# Base_Schematic.net
KiCad netlist of a schematic drawn in Altium Designer
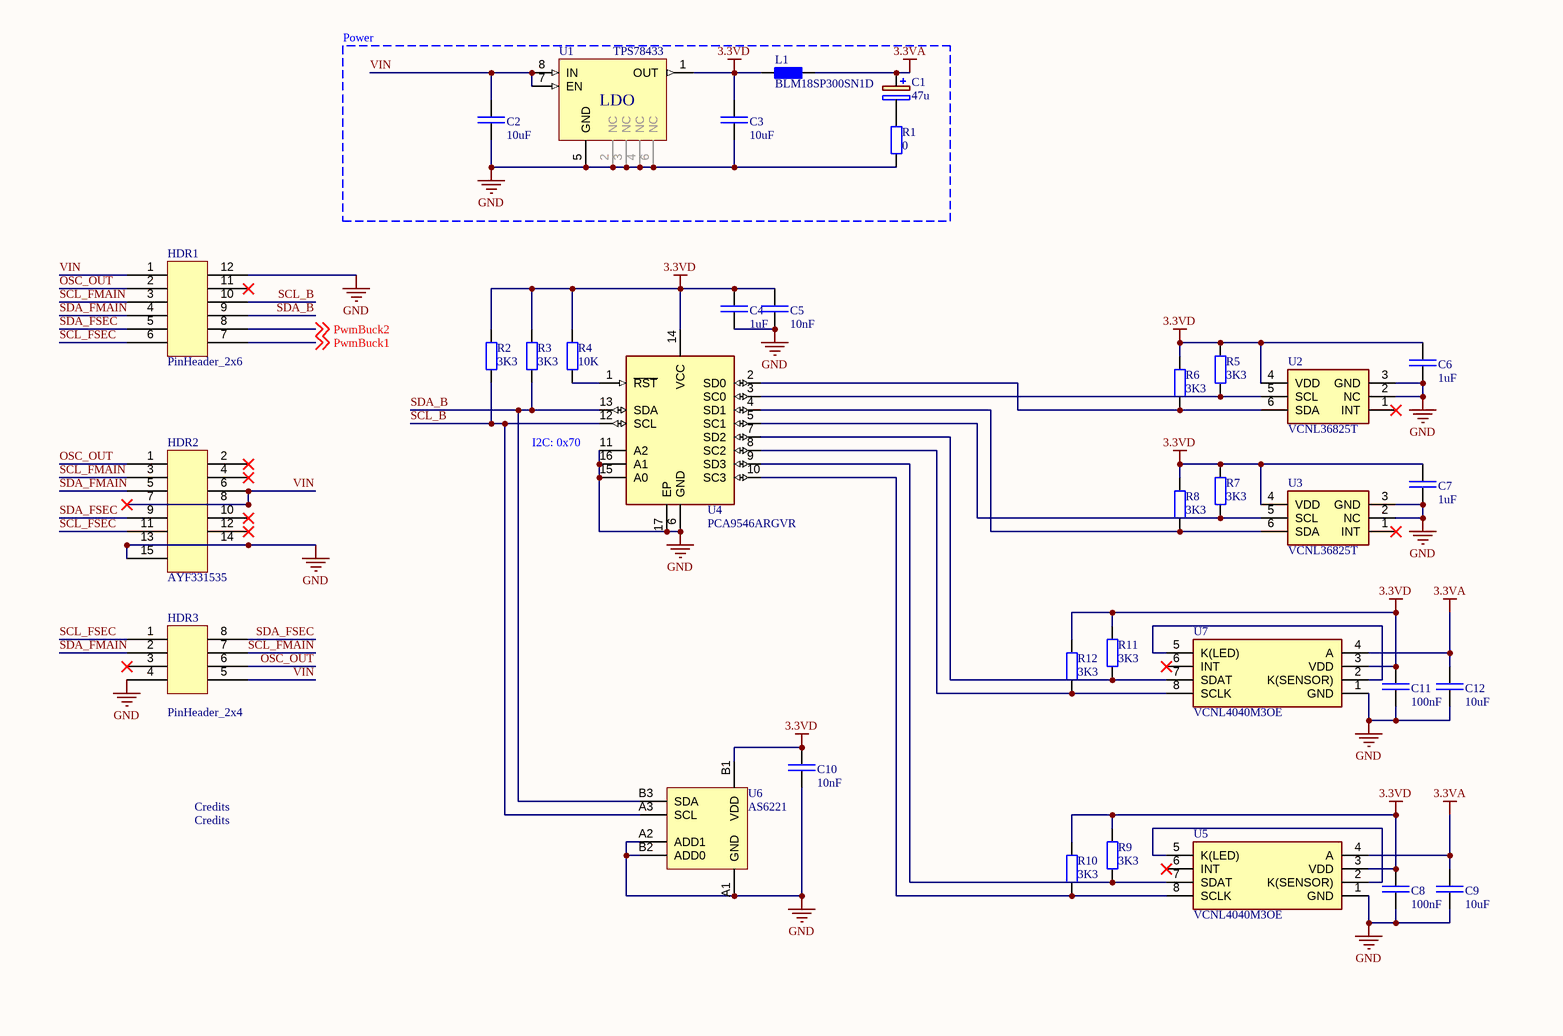
[diagram p0: Base_Schematic.SchDoc]

(export (version "E")
  (design (tool "Eeschema 10.0.6"))
  (components
    (comp (ref "C1")
      (value "47u")
      (footprint "CAPAE7366X61N")
      (description "Aluminium Electrolytic Capacitors - SMD 47uF 25V")
      (libsource (lib "Base_Symbols") (part "EEE-FK1E470P"))
    )
    (comp (ref "C2")
      (value "10uF")
      (footprint "CAP_SM0805_YAGEOCC2_N")
      (description "CAP 10uF SM0805 X5R 16V YAGEO CC2")
      (fields
        (field (name "MANUFACTURER") "Yageo")
        (field (name "MANUFACTURER PART NUMBER") "CC0805KKX7R8BB225")
      )
      (libsource (lib "Base_Symbols") (part "CC0805KKX5R8BB106"))
    )
    (comp (ref "C3")
      (value "10uF")
      (footprint "CAP_SM0805_YAGEOCC2_N")
      (description "CAP 10uF SM0805 X5R 16V YAGEO CC2")
      (fields
        (field (name "MANUFACTURER") "Yageo")
        (field (name "MANUFACTURER PART NUMBER") "CC0805KKX7R8BB225")
      )
      (libsource (lib "Base_Symbols") (part "CC0805KKX5R8BB106"))
    )
    (comp (ref "C4")
      (value "1uF")
      (footprint "CAP_SM0805_YAGEOCC2_N")
      (description "CAP 1uF SM0805 X7R 25V YAGEO CC2")
      (fields
        (field (name "MANUFACTURER") "Yageo")
        (field (name "MANUFACTURER PART NUMBER") "CC0805KKX7R8BB105")
      )
      (libsource (lib "Base_Symbols") (part "CC0805KKX7R8BB105"))
    )
    (comp (ref "C5")
      (value "10nF")
      (footprint "CAP_SM0402_YAGEOCC2_N")
      (description "CAP 10nF SM0402 X7R 50V YAGEO CC2")
      (fields
        (field (name "MANUFACTURER") "Yageo")
        (field (name "MANUFACTURER PART NUMBER") "CC0603KRX7R9BB103")
      )
      (libsource (lib "Base_Symbols") (part "CC0402KRX7R9BB103"))
    )
    (comp (ref "C6")
      (value "1uF")
      (footprint "CAP_SM0805_YAGEOCC2_N")
      (description "CAP 1uF SM0805 X7R 25V YAGEO CC2")
      (fields
        (field (name "MANUFACTURER") "Yageo")
        (field (name "MANUFACTURER PART NUMBER") "CC0805KKX7R8BB105")
      )
      (libsource (lib "Base_Symbols") (part "CC0805KKX7R8BB105"))
    )
    (comp (ref "C7")
      (value "1uF")
      (footprint "CAP_SM0805_YAGEOCC2_N")
      (description "CAP 1uF SM0805 X7R 25V YAGEO CC2")
      (fields
        (field (name "MANUFACTURER") "Yageo")
        (field (name "MANUFACTURER PART NUMBER") "CC0805KKX7R8BB105")
      )
      (libsource (lib "Base_Symbols") (part "CC0805KKX7R8BB105"))
    )
    (comp (ref "C8")
      (value "100nF")
      (footprint "CAP_SM0603_YAGEOCC2_N")
      (description "CAP 100nF SM0603 X7R 50V YAGEO CC2")
      (fields
        (field (name "MANUFACTURER") "Yageo")
        (field (name "MANUFACTURER PART NUMBER") "CC0603KRX7R9BB104")
      )
      (libsource (lib "Base_Symbols") (part "CC0603KRX7R9BB104"))
    )
    (comp (ref "C9")
      (value "10uF")
      (footprint "CAP_SM0805_YAGEOCC2_N")
      (description "CAP 10uF SM0805 X5R 16V YAGEO CC2")
      (fields
        (field (name "MANUFACTURER") "Yageo")
        (field (name "MANUFACTURER PART NUMBER") "CC0805KKX7R8BB225")
      )
      (libsource (lib "Base_Symbols") (part "CC0805KKX5R8BB106"))
    )
    (comp (ref "C10")
      (value "10nF")
      (footprint "CAP_SM0402_YAGEOCC2_N")
      (description "CAP 10nF SM0402 X7R 50V YAGEO CC2")
      (fields
        (field (name "MANUFACTURER") "Yageo")
        (field (name "MANUFACTURER PART NUMBER") "CC0603KRX7R9BB103")
      )
      (libsource (lib "Base_Symbols") (part "CC0402KRX7R9BB103"))
    )
    (comp (ref "C11")
      (value "100nF")
      (footprint "CAP_SM0603_YAGEOCC2_N")
      (description "CAP 100nF SM0603 X7R 50V YAGEO CC2")
      (fields
        (field (name "MANUFACTURER") "Yageo")
        (field (name "MANUFACTURER PART NUMBER") "CC0603KRX7R9BB104")
      )
      (libsource (lib "Base_Symbols") (part "CC0603KRX7R9BB104"))
    )
    (comp (ref "C12")
      (value "10uF")
      (footprint "CAP_SM0805_YAGEOCC2_N")
      (description "CAP 10uF SM0805 X5R 16V YAGEO CC2")
      (fields
        (field (name "MANUFACTURER") "Yageo")
        (field (name "MANUFACTURER PART NUMBER") "CC0805KKX7R8BB225")
      )
      (libsource (lib "Base_Symbols") (part "CC0805KKX5R8BB106"))
    )
    (comp (ref "Credit")
      (value "Credits")
      (footprint "CREDITS_CU+TS_SIGNED")
      (libsource (lib "Base_Symbols") (part "Credits"))
    )
    (comp (ref "HDR1")
      (value "PinHeader_2x6")
      (footprint "PinHeader_2x6_2.54mm")
      (description "PinHeader_2x6 2.54mm Pitch")
      (libsource (lib "Base_Symbols") (part "PinHeader_2x6_2.54mm"))
    )
    (comp (ref "HDR2")
      (value "AYF331535")
      (footprint "AYF331535 _Reverse")
      (description "AYF331535 FFC & FPC-Steckverbinder CONNECTOR SURFACE MOUNT")
      (libsource (lib "Base_Symbols") (part "AYF331535"))
    )
    (comp (ref "HDR3")
      (value "PinHeader_2x4")
      (footprint "PinHeader_2x4_2.54mm")
      (description "PinHeader_2x4 2.54mm Pitch")
      (libsource (lib "Base_Symbols") (part "PinHeader_2x4_2.54mm"))
    )
    (comp (ref "L1")
      (value "BLM18SP300SN1D")
      (footprint "Chip2PinSM127P600-8N")
      (description "Ferrite Beads 0603 30ohm 10% 6A")
      (fields (field (name "MOUSER PART NUMBER") "81-BLM18SP300SN1D"))
      (libsource (lib "Base_Symbols") (part "BLM18SP300SN1D"))
    )
    (comp (ref "R1")
      (value "0")
      (footprint "RES_SM0603_YAGEORC_N")
      (description "RES 0R SM0603 YAGEO RC_L")
      (fields
        (field (name "MANUFACTURER") "Yageo")
        (field (name "MANUFACTURER PART NUMBER") "RC0603FR-0710KL")
      )
      (libsource (lib "Base_Symbols") (part "RC0603FR-070RL"))
    )
    (comp (ref "R2")
      (value "3K3")
      (footprint "RES_SM0603_YAGEORC_N")
      (description "RES 3K3 SM0603 YAGEO RC_L")
      (fields
        (field (name "MANUFACTURER") "Yageo")
        (field (name "MANUFACTURER PART NUMBER") "RC0603FR-0710KL")
      )
      (libsource (lib "") (part "RC0603FR-073K3L_1"))
    )
    (comp (ref "R3")
      (value "3K3")
      (footprint "RES_SM0603_YAGEORC_N")
      (description "RES 3K3 SM0603 YAGEO RC_L")
      (fields
        (field (name "MANUFACTURER") "Yageo")
        (field (name "MANUFACTURER PART NUMBER") "RC0603FR-0710KL")
      )
      (libsource (lib "") (part "RC0603FR-073K3L_1"))
    )
    (comp (ref "R4")
      (value "10K")
      (footprint "RES_SM0603_YAGEORC_N")
      (description "RES 10K SM0603 YAGEO RC_L")
      (fields
        (field (name "MANUFACTURER") "Yageo")
        (field (name "MANUFACTURER PART NUMBER") "RC0603FR-0710KL")
      )
      (libsource (lib "Base_Symbols") (part "RC0603FR-0710KL"))
    )
    (comp (ref "R5")
      (value "3K3")
      (footprint "RES_SM0603_YAGEORC_N")
      (description "RES 3K3 SM0603 YAGEO RC_L")
      (fields
        (field (name "MANUFACTURER") "Yageo")
        (field (name "MANUFACTURER PART NUMBER") "RC0603FR-0710KL")
      )
      (libsource (lib "Base_Symbols") (part "RC0603FR-073K3L"))
    )
    (comp (ref "R6")
      (value "3K3")
      (footprint "RES_SM0603_YAGEORC_N")
      (description "RES 3K3 SM0603 YAGEO RC_L")
      (fields
        (field (name "MANUFACTURER") "Yageo")
        (field (name "MANUFACTURER PART NUMBER") "RC0603FR-0710KL")
      )
      (libsource (lib "Base_Symbols") (part "RC0603FR-073K3L"))
    )
    (comp (ref "R7")
      (value "3K3")
      (footprint "RES_SM0603_YAGEORC_N")
      (description "RES 3K3 SM0603 YAGEO RC_L")
      (fields
        (field (name "MANUFACTURER") "Yageo")
        (field (name "MANUFACTURER PART NUMBER") "RC0603FR-0710KL")
      )
      (libsource (lib "Base_Symbols") (part "RC0603FR-073K3L"))
    )
    (comp (ref "R8")
      (value "3K3")
      (footprint "RES_SM0603_YAGEORC_N")
      (description "RES 3K3 SM0603 YAGEO RC_L")
      (fields
        (field (name "MANUFACTURER") "Yageo")
        (field (name "MANUFACTURER PART NUMBER") "RC0603FR-0710KL")
      )
      (libsource (lib "Base_Symbols") (part "RC0603FR-073K3L"))
    )
    (comp (ref "R9")
      (value "3K3")
      (footprint "RES_SM0603_YAGEORC_N")
      (description "RES 3K3 SM0603 YAGEO RC_L")
      (fields
        (field (name "MANUFACTURER") "Yageo")
        (field (name "MANUFACTURER PART NUMBER") "RC0603FR-0710KL")
      )
      (libsource (lib "Base_Symbols") (part "RC0603FR-073K3L"))
    )
    (comp (ref "R10")
      (value "3K3")
      (footprint "RES_SM0603_YAGEORC_N")
      (description "RES 3K3 SM0603 YAGEO RC_L")
      (fields
        (field (name "MANUFACTURER") "Yageo")
        (field (name "MANUFACTURER PART NUMBER") "RC0603FR-0710KL")
      )
      (libsource (lib "Base_Symbols") (part "RC0603FR-073K3L"))
    )
    (comp (ref "R11")
      (value "3K3")
      (footprint "RES_SM0603_YAGEORC_N")
      (description "RES 3K3 SM0603 YAGEO RC_L")
      (fields
        (field (name "MANUFACTURER") "Yageo")
        (field (name "MANUFACTURER PART NUMBER") "RC0603FR-0710KL")
      )
      (libsource (lib "Base_Symbols") (part "RC0603FR-073K3L"))
    )
    (comp (ref "R12")
      (value "3K3")
      (footprint "RES_SM0603_YAGEORC_N")
      (description "RES 3K3 SM0603 YAGEO RC_L")
      (fields
        (field (name "MANUFACTURER") "Yageo")
        (field (name "MANUFACTURER PART NUMBER") "RC0603FR-0710KL")
      )
      (libsource (lib "Base_Symbols") (part "RC0603FR-073K3L"))
    )
    (comp (ref "U1")
      (value "TPS78433")
      (footprint "TPS784xxxQDRBRQ1_SON")
      (libsource (lib "Base_Symbols") (part "TPS78433QWDRBRQ1"))
    )
    (comp (ref "U2")
      (value "VCNL36825T")
      (footprint "VCNL36825T")
      (description "Proximity Sensors PROX SENS INTER VCSEL I2C-E4, IC SENSORS")
      (fields (field (name "MOUSER PART NUMBER") "78-VCNL36825T"))
      (libsource (lib "Base_Symbols") (part "VCNL36825T"))
    )
    (comp (ref "U3")
      (value "VCNL36825T")
      (footprint "VCNL36825T")
      (description "Proximity Sensors PROX SENS INTER VCSEL I2C-E4, IC SENSORS")
      (fields (field (name "MOUSER PART NUMBER") "78-VCNL36825T"))
      (libsource (lib "Base_Symbols") (part "VCNL36825T"))
    )
    (comp (ref "U4")
      (value "PCA9546ARGVR")
      (footprint "QFN65P400X400X100-17N-D")
      (description "4-Channel I2C And SMBus Switch With Reset Functions")
      (fields (field (name "MOUSER PART NUMBER") "595-PCA9546ARGVR"))
      (libsource (lib "Base_Symbols") (part "PCA9546ARGVR"))
    )
    (comp (ref "U5")
      (value "VCNL4040M3OE")
      (footprint "VCNL4040M3OE")
      (fields (field (name "MOUSER PART NUMBER") "78-VCNL4040M3OE"))
      (libsource (lib "Base_Symbols") (part "VCNL4040M3OE"))
    )
    (comp (ref "U6")
      (value "AS6221")
      (footprint "AS6221_BGA_LargePads")
      (description "AS6221 Temperature Sensor Digital -40°C ~ 125°C 16b 6-WLCSP (1.5x1.03)")
      (libsource (lib "Base_Symbols") (part "AS6221-AWLT-S"))
    )
    (comp (ref "U7")
      (value "VCNL4040M3OE")
      (footprint "VCNL4040M3OE")
      (fields (field (name "MOUSER PART NUMBER") "78-VCNL4040M3OE"))
      (libsource (lib "Base_Symbols") (part "VCNL4040M3OE"))
    )
  )
  (nets
    (net (code "1") (name "/OSC_OUT") (class "Default")
      (node (ref "HDR1") (pin "2") (pintype "passive"))
      (node (ref "HDR2") (pin "1") (pintype "passive"))
      (node (ref "HDR3") (pin "6") (pintype "passive"))
    )
    (net (code "2") (name "/SCL_B") (class "Default")
      (node (ref "HDR1") (pin "10") (pintype "passive"))
      (node (ref "R2") (pin "2") (pintype "passive"))
      (node (ref "U4") (pin "12") (pinfunction "SCL_12") (pintype "bidirectional"))
      (node (ref "U6") (pin "A3") (pinfunction "SCL_A3") (pintype "passive"))
    )
    (net (code "3") (name "/SCL_FMAIN") (class "Default")
      (node (ref "HDR1") (pin "3") (pintype "passive"))
      (node (ref "HDR2") (pin "3") (pintype "passive"))
      (node (ref "HDR3") (pin "7") (pintype "passive"))
    )
    (net (code "4") (name "/SCL_FSEC") (class "Default")
      (node (ref "HDR1") (pin "6") (pintype "passive"))
      (node (ref "HDR2") (pin "11") (pintype "passive"))
      (node (ref "HDR3") (pin "1") (pintype "passive"))
    )
    (net (code "5") (name "/SDA_B") (class "Default")
      (node (ref "HDR1") (pin "9") (pintype "passive"))
      (node (ref "R3") (pin "2") (pintype "passive"))
      (node (ref "U4") (pin "13") (pinfunction "SDA_13") (pintype "bidirectional"))
      (node (ref "U6") (pin "B3") (pinfunction "SDA_B3") (pintype "passive"))
    )
    (net (code "6") (name "/SDA_FMAIN") (class "Default")
      (node (ref "HDR1") (pin "4") (pintype "passive"))
      (node (ref "HDR2") (pin "5") (pintype "passive"))
      (node (ref "HDR3") (pin "2") (pintype "passive"))
    )
    (net (code "7") (name "/SDA_FSEC") (class "Default")
      (node (ref "HDR1") (pin "5") (pintype "passive"))
      (node (ref "HDR2") (pin "9") (pintype "passive"))
      (node (ref "HDR3") (pin "8") (pintype "passive"))
    )
    (net (code "8") (name "/VIN") (class "Default")
      (node (ref "C2") (pin "1") (pintype "passive"))
      (node (ref "HDR1") (pin "1") (pintype "passive"))
      (node (ref "HDR2") (pin "6") (pintype "passive"))
      (node (ref "HDR2") (pin "7") (pintype "passive"))
      (node (ref "HDR2") (pin "8") (pintype "passive"))
      (node (ref "HDR3") (pin "5") (pintype "passive"))
      (node (ref "U1") (pin "7") (pinfunction "EN_7") (pintype "input"))
      (node (ref "U1") (pin "8") (pinfunction "IN_8") (pintype "input"))
    )
    (net (code "9") (name "3.3VA") (class "Default")
      (node (ref "C1") (pin "1") (pinfunction "+_1") (pintype "passive"))
      (node (ref "C12") (pin "1") (pintype "passive"))
      (node (ref "C9") (pin "1") (pintype "passive"))
      (node (ref "L1") (pin "2") (pintype "passive"))
      (node (ref "U5") (pin "4") (pinfunction "A_4") (pintype "passive"))
      (node (ref "U7") (pin "4") (pinfunction "A_4") (pintype "passive"))
    )
    (net (code "10") (name "3.3VD") (class "Default")
      (node (ref "C10") (pin "1") (pintype "passive"))
      (node (ref "C11") (pin "1") (pintype "passive"))
      (node (ref "C3") (pin "1") (pintype "passive"))
      (node (ref "C4") (pin "1") (pintype "passive"))
      (node (ref "C5") (pin "1") (pintype "passive"))
      (node (ref "C6") (pin "1") (pintype "passive"))
      (node (ref "C7") (pin "1") (pintype "passive"))
      (node (ref "C8") (pin "1") (pintype "passive"))
      (node (ref "L1") (pin "1") (pintype "passive"))
      (node (ref "R10") (pin "2") (pintype "passive"))
      (node (ref "R11") (pin "2") (pintype "passive"))
      (node (ref "R12") (pin "2") (pintype "passive"))
      (node (ref "R2") (pin "1") (pintype "passive"))
      (node (ref "R3") (pin "1") (pintype "passive"))
      (node (ref "R4") (pin "1") (pintype "passive"))
      (node (ref "R5") (pin "2") (pintype "passive"))
      (node (ref "R6") (pin "2") (pintype "passive"))
      (node (ref "R7") (pin "2") (pintype "passive"))
      (node (ref "R8") (pin "2") (pintype "passive"))
      (node (ref "R9") (pin "2") (pintype "passive"))
      (node (ref "U1") (pin "1") (pinfunction "OUT_1") (pintype "output"))
      (node (ref "U2") (pin "4") (pinfunction "VDD_4") (pintype "passive"))
      (node (ref "U3") (pin "4") (pinfunction "VDD_4") (pintype "passive"))
      (node (ref "U4") (pin "14") (pinfunction "VCC_14") (pintype "passive"))
      (node (ref "U5") (pin "3") (pinfunction "VDD_3") (pintype "passive"))
      (node (ref "U6") (pin "B1") (pinfunction "VDD_B1") (pintype "passive"))
      (node (ref "U7") (pin "3") (pinfunction "VDD_3") (pintype "passive"))
    )
    (net (code "11") (name "GND") (class "Default")
      (node (ref "C10") (pin "2") (pintype "passive"))
      (node (ref "C11") (pin "2") (pintype "passive"))
      (node (ref "C12") (pin "2") (pintype "passive"))
      (node (ref "C2") (pin "2") (pintype "passive"))
      (node (ref "C3") (pin "2") (pintype "passive"))
      (node (ref "C4") (pin "2") (pintype "passive"))
      (node (ref "C5") (pin "2") (pintype "passive"))
      (node (ref "C6") (pin "2") (pintype "passive"))
      (node (ref "C7") (pin "2") (pintype "passive"))
      (node (ref "C8") (pin "2") (pintype "passive"))
      (node (ref "C9") (pin "2") (pintype "passive"))
      (node (ref "HDR1") (pin "12") (pintype "passive"))
      (node (ref "HDR2") (pin "13") (pintype "passive"))
      (node (ref "HDR2") (pin "14") (pintype "passive"))
      (node (ref "HDR2") (pin "15") (pintype "passive"))
      (node (ref "HDR3") (pin "4") (pintype "passive"))
      (node (ref "R1") (pin "1") (pintype "passive"))
      (node (ref "U1") (pin "2") (pinfunction "NC_2") (pintype "passive"))
      (node (ref "U1") (pin "3") (pinfunction "NC_3") (pintype "passive"))
      (node (ref "U1") (pin "4") (pinfunction "NC_4") (pintype "passive"))
      (node (ref "U1") (pin "5") (pinfunction "GND_5") (pintype "passive"))
      (node (ref "U1") (pin "6") (pinfunction "NC_6") (pintype "passive"))
      (node (ref "U2") (pin "2") (pinfunction "NC_2") (pintype "passive"))
      (node (ref "U2") (pin "3") (pinfunction "GND_3") (pintype "passive"))
      (node (ref "U3") (pin "2") (pinfunction "NC_2") (pintype "passive"))
      (node (ref "U3") (pin "3") (pinfunction "GND_3") (pintype "passive"))
      (node (ref "U4") (pin "11") (pinfunction "A2_11") (pintype "passive"))
      (node (ref "U4") (pin "15") (pinfunction "A0_15") (pintype "passive"))
      (node (ref "U4") (pin "16") (pinfunction "A1_16") (pintype "passive"))
      (node (ref "U4") (pin "17") (pinfunction "EP_17") (pintype "passive"))
      (node (ref "U4") (pin "6") (pinfunction "GND_6") (pintype "passive"))
      (node (ref "U5") (pin "1") (pinfunction "GND_1") (pintype "passive"))
      (node (ref "U6") (pin "A1") (pinfunction "GND_A1") (pintype "passive"))
      (node (ref "U6") (pin "A2") (pinfunction "ADD1_A2") (pintype "passive"))
      (node (ref "U6") (pin "B2") (pinfunction "ADD0_B2") (pintype "passive"))
      (node (ref "U7") (pin "1") (pinfunction "GND_1") (pintype "passive"))
    )
    (net (code "12") (name "Net-(C1--)") (class "Default")
      (node (ref "C1") (pin "2") (pinfunction "-_2") (pintype "passive"))
      (node (ref "R1") (pin "2") (pintype "passive"))
    )
    (net (code "13") (name "Net-(U2-SCL)") (class "Default")
      (node (ref "R5") (pin "1") (pintype "passive"))
      (node (ref "U2") (pin "5") (pinfunction "SCL_5") (pintype "passive"))
      (node (ref "U4") (pin "3") (pinfunction "SC0_3") (pintype "bidirectional"))
    )
    (net (code "14") (name "Net-(U2-SDA)") (class "Default")
      (node (ref "R6") (pin "1") (pintype "passive"))
      (node (ref "U2") (pin "6") (pinfunction "SDA_6") (pintype "passive"))
      (node (ref "U4") (pin "2") (pinfunction "SD0_2") (pintype "bidirectional"))
    )
    (net (code "15") (name "Net-(U3-SCL)") (class "Default")
      (node (ref "R7") (pin "1") (pintype "passive"))
      (node (ref "U3") (pin "5") (pinfunction "SCL_5") (pintype "passive"))
      (node (ref "U4") (pin "5") (pinfunction "SC1_5") (pintype "bidirectional"))
    )
    (net (code "16") (name "Net-(U3-SDA)") (class "Default")
      (node (ref "R8") (pin "1") (pintype "passive"))
      (node (ref "U3") (pin "6") (pinfunction "SDA_6") (pintype "passive"))
      (node (ref "U4") (pin "4") (pinfunction "SD1_4") (pintype "bidirectional"))
    )
    (net (code "17") (name "Net-(U4-SC2)") (class "Default")
      (node (ref "R12") (pin "1") (pintype "passive"))
      (node (ref "U4") (pin "8") (pinfunction "SC2_8") (pintype "bidirectional"))
      (node (ref "U7") (pin "8") (pinfunction "SCLK_8") (pintype "passive"))
    )
    (net (code "18") (name "Net-(U4-SC3)") (class "Default")
      (node (ref "R10") (pin "1") (pintype "passive"))
      (node (ref "U4") (pin "10") (pinfunction "SC3_10") (pintype "bidirectional"))
      (node (ref "U5") (pin "8") (pinfunction "SCLK_8") (pintype "passive"))
    )
    (net (code "19") (name "Net-(U4-SD2)") (class "Default")
      (node (ref "R11") (pin "1") (pintype "passive"))
      (node (ref "U4") (pin "7") (pinfunction "SD2_7") (pintype "bidirectional"))
      (node (ref "U7") (pin "7") (pinfunction "SDAT_7") (pintype "passive"))
    )
    (net (code "20") (name "Net-(U4-SD3)") (class "Default")
      (node (ref "R9") (pin "1") (pintype "passive"))
      (node (ref "U4") (pin "9") (pinfunction "SD3_9") (pintype "bidirectional"))
      (node (ref "U5") (pin "7") (pinfunction "SDAT_7") (pintype "passive"))
    )
    (net (code "21") (name "Net-(U4-~{RST})") (class "Default")
      (node (ref "R4") (pin "2") (pintype "passive"))
      (node (ref "U4") (pin "1") (pinfunction "~{RST}_1") (pintype "input"))
    )
    (net (code "22") (name "Net-(U5-K(LED))") (class "Default")
      (node (ref "U5") (pin "2") (pinfunction "K(SENSOR)_2") (pintype "passive"))
      (node (ref "U5") (pin "5") (pinfunction "K(LED)_5") (pintype "passive"))
    )
    (net (code "23") (name "Net-(U7-K(LED))") (class "Default")
      (node (ref "U7") (pin "2") (pinfunction "K(SENSOR)_2") (pintype "passive"))
      (node (ref "U7") (pin "5") (pinfunction "K(LED)_5") (pintype "passive"))
    )
    (net (code "24") (name "PwmBuck1") (class "Default") (node (ref "HDR1") (pin "7") (pintype "passive")))
    (net (code "25") (name "PwmBuck2") (class "Default") (node (ref "HDR1") (pin "8") (pintype "passive")))
    (net (code "26") (name "unconnected-(HDR1-Pad11)") (class "Default")
      (node (ref "HDR1") (pin "11") (pintype "passive+no_connect"))
    )
    (net (code "27") (name "unconnected-(HDR2-Pad2)") (class "Default")
      (node (ref "HDR2") (pin "2") (pintype "passive+no_connect"))
    )
    (net (code "28") (name "unconnected-(HDR2-Pad4)") (class "Default")
      (node (ref "HDR2") (pin "4") (pintype "passive+no_connect"))
    )
    (net (code "29") (name "unconnected-(HDR2-Pad10)") (class "Default")
      (node (ref "HDR2") (pin "10") (pintype "passive+no_connect"))
    )
    (net (code "30") (name "unconnected-(HDR2-Pad12)") (class "Default")
      (node (ref "HDR2") (pin "12") (pintype "passive+no_connect"))
    )
    (net (code "31") (name "unconnected-(HDR3-Pad3)") (class "Default")
      (node (ref "HDR3") (pin "3") (pintype "passive+no_connect"))
    )
    (net (code "32") (name "unconnected-(U2-INT-Pad1)") (class "Default")
      (node (ref "U2") (pin "1") (pinfunction "INT_1") (pintype "passive+no_connect"))
    )
    (net (code "33") (name "unconnected-(U3-INT-Pad1)") (class "Default")
      (node (ref "U3") (pin "1") (pinfunction "INT_1") (pintype "passive+no_connect"))
    )
    (net (code "34") (name "unconnected-(U5-INT-Pad6)") (class "Default")
      (node (ref "U5") (pin "6") (pinfunction "INT_6") (pintype "passive+no_connect"))
    )
    (net (code "35") (name "unconnected-(U7-INT-Pad6)") (class "Default")
      (node (ref "U7") (pin "6") (pinfunction "INT_6") (pintype "passive+no_connect"))
    )
  )
)
